# PFC.net
KiCad netlist of a schematic drawn in Altium Designer
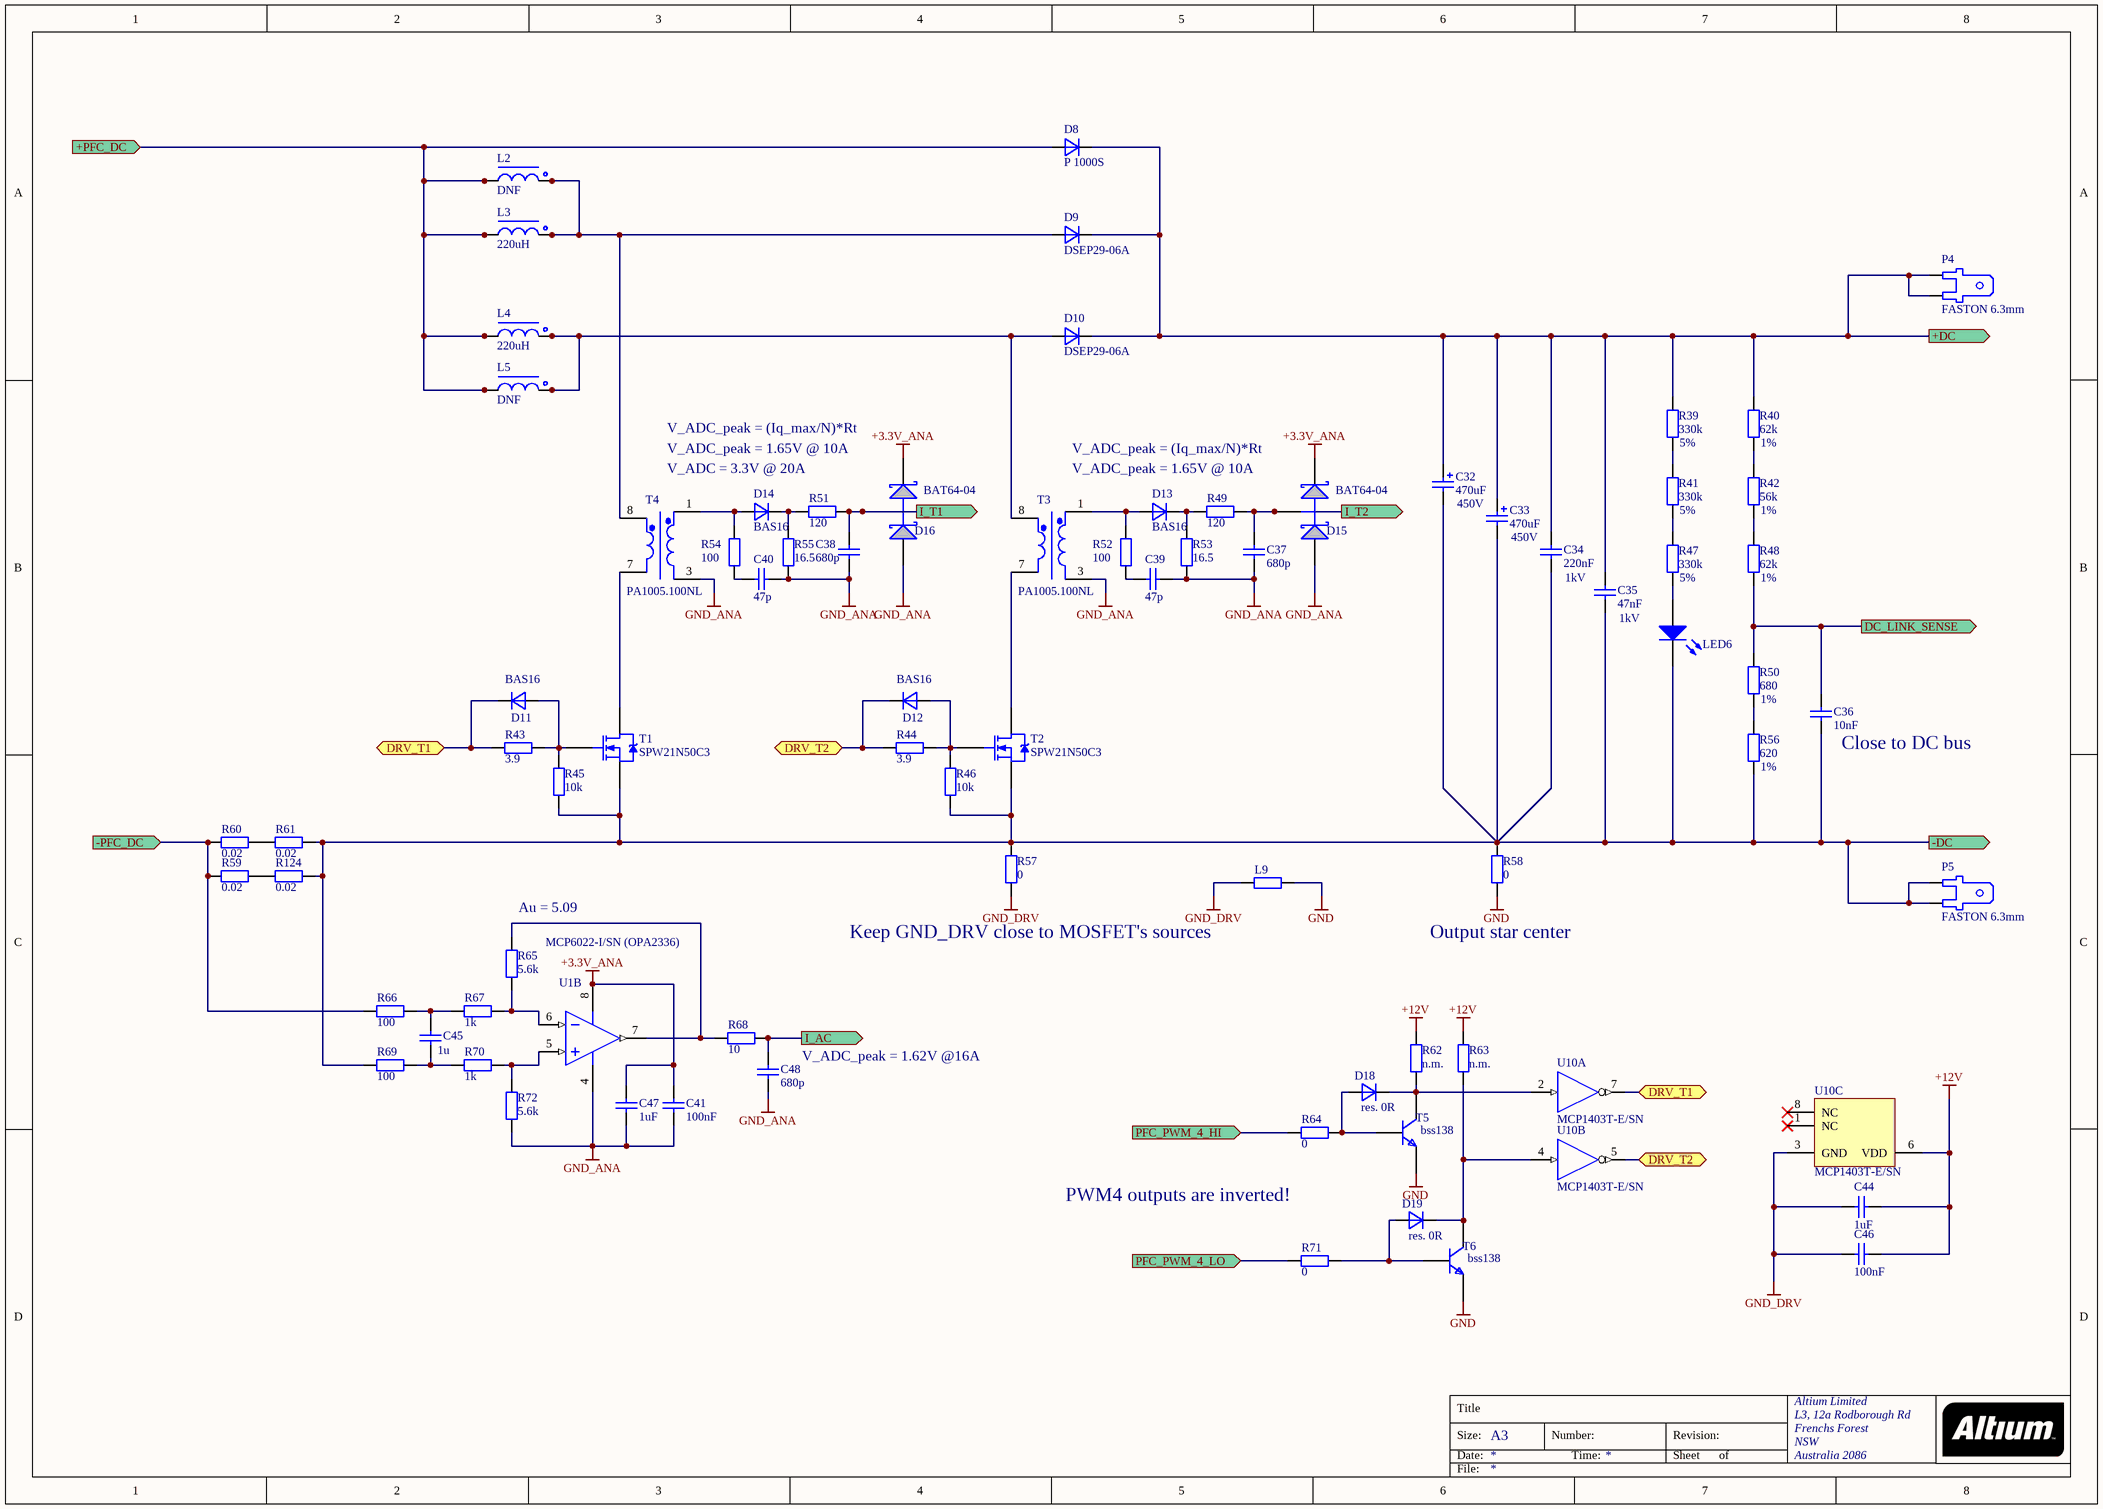
[diagram p0: PFC.SchDoc]

(export (version "E")
  (design (tool "Eeschema 10.0.6"))
  (components
    (comp (ref "C32")
      (value "470uF")
      (footprint "CAPR 52X35")
      (fields (field (name "VOLTAGE") "450V") (field (name "Comment") "Cap"))
      (libsource (lib "Capacitors") (part "Cap pol"))
    )
    (comp (ref "C33")
      (value "470uF")
      (footprint "CAPR 52X35")
      (fields (field (name "VOLTAGE") "450V") (field (name "Comment") "Cap"))
      (libsource (lib "Capacitors") (part "Cap pol"))
    )
    (comp (ref "C34")
      (value "220nF")
      (footprint "RECT 31.0X11.0 RM27.5")
      (fields
        (field (name "VOLTAGE") "1kV")
        (field (name "MANUFACTURER") "EPCOS")
        (field (name "Comment") "Cap")
      )
      (libsource (lib "Capacitors") (part "Cap"))
    )
    (comp (ref "C35")
      (value "47nF")
      (footprint "RECT 26.5X7.0 RM22.5")
      (fields
        (field (name "VOLTAGE") "1kV")
        (field (name "MANUFACTURER") "Epcos")
        (field (name "Comment") "Cap")
      )
      (libsource (lib "Capacitors") (part "Cap"))
    )
    (comp (ref "C36")
      (value "10nF")
      (footprint "1206_REFLOW")
      (fields (field (name "Comment") "Cap 1206"))
      (libsource (lib "Capacitors") (part "Cap 1206"))
    )
    (comp (ref "C37")
      (value "680p")
      (footprint "1206_REFLOW")
      (fields (field (name "Comment") "Cap 1206"))
      (libsource (lib "Capacitors") (part "Cap 1206"))
    )
    (comp (ref "C38")
      (value "680p")
      (footprint "1206_REFLOW")
      (fields (field (name "Comment") "Cap 1206"))
      (libsource (lib "Capacitors") (part "Cap 1206"))
    )
    (comp (ref "C39")
      (value "47p")
      (footprint "1206_REFLOW")
      (fields (field (name "Comment") "Cap 1206"))
      (libsource (lib "Capacitors") (part "Cap 1206"))
    )
    (comp (ref "C40")
      (value "47p")
      (footprint "1206_REFLOW")
      (fields (field (name "Comment") "Cap 1206"))
      (libsource (lib "Capacitors") (part "Cap 1206"))
    )
    (comp (ref "C41")
      (value "100nF")
      (footprint "1206_REFLOW")
      (fields (field (name "Comment") "Cap"))
      (libsource (lib "Capacitors") (part "Cap"))
    )
    (comp (ref "C44")
      (value "1uF")
      (footprint "1206_REFLOW")
      (fields (field (name "Comment") "Cap 1206"))
      (libsource (lib "Capacitors") (part "Cap 1206"))
    )
    (comp (ref "C45")
      (value "1u")
      (footprint "1206_REFLOW")
      (fields (field (name "Comment") "Cap"))
      (libsource (lib "Capacitors") (part "Cap"))
    )
    (comp (ref "C46")
      (value "100nF")
      (footprint "1206_REFLOW")
      (fields (field (name "Comment") "Cap 1206"))
      (libsource (lib "Capacitors") (part "Cap 1206"))
    )
    (comp (ref "C47")
      (value "1uF")
      (footprint "1206_REFLOW")
      (fields (field (name "Comment") "Cap"))
      (libsource (lib "Capacitors") (part "Cap"))
    )
    (comp (ref "C48")
      (value "680p")
      (footprint "1206_REFLOW")
      (fields (field (name "Comment") "Cap"))
      (libsource (lib "Capacitors") (part "Cap"))
    )
    (comp (ref "D8")
      (value "P 1000S")
      (footprint "P 1000 S")
      (description "Standard silicon rectifier  diode")
      (libsource (lib "Diode") (part "P 1000S"))
    )
    (comp (ref "D9")
      (value "DSEP29-06A")
      (footprint "Diode TO-220AC-HV")
      (description "HiPerFREDTM Epitaxial Diode with soft recovery")
      (libsource (lib "Diode") (part "DSEP29-06A"))
    )
    (comp (ref "D10")
      (value "DSEP29-06A")
      (footprint "Diode TO-220AC-HV")
      (description "HiPerFREDTM Epitaxial Diode with soft recovery")
      (libsource (lib "Diode") (part "DSEP29-06A"))
    )
    (comp (ref "D11")
      (value "BAS16")
      (footprint "SOT23_HIS_Primary")
      (description "DIODE, SINGLE SOT-23")
      (fields (field (name "MANUFACTURER") "Any"))
      (libsource (lib "") (part "BAS16_1"))
    )
    (comp (ref "D12")
      (value "BAS16")
      (footprint "SOT23_HIS_Primary")
      (description "DIODE, SINGLE SOT-23")
      (fields (field (name "MANUFACTURER") "Any"))
      (libsource (lib "") (part "BAS16_1"))
    )
    (comp (ref "D13")
      (value "BAS16")
      (footprint "SOT23_HIS_Primary")
      (description "DIODE, SINGLE SOT-23")
      (fields (field (name "MANUFACTURER") "Any"))
      (libsource (lib "Diode") (part "BAS16"))
    )
    (comp (ref "D14")
      (value "BAS16")
      (footprint "SOT23_HIS_Primary")
      (description "DIODE, SINGLE SOT-23")
      (fields (field (name "MANUFACTURER") "Any"))
      (libsource (lib "Diode") (part "BAS16"))
    )
    (comp (ref "D15")
      (value "BAT64-04")
      (footprint "SOT23_HIS_Primary")
      (description "Silicon Schottky Diodes")
      (fields (field (name "MANUFACTURER") "INF") (field (name "PUBLISHER") "Altium Limited"))
      (libsource (lib "Diode") (part "BAT64-04"))
    )
    (comp (ref "D16")
      (value "BAT64-04")
      (footprint "SOT23_HIS_Primary")
      (description "Silicon Schottky Diodes")
      (fields (field (name "MANUFACTURER") "INF") (field (name "PUBLISHER") "Altium Limited"))
      (libsource (lib "Diode") (part "BAT64-04"))
    )
    (comp (ref "D18")
      (value "res. 0R")
      (footprint "SOT23_HIS_Primary")
      (description "DIODE, SINGLE SOT-23")
      (fields (field (name "MANUFACTURER") "Any") (field (name "Comment") "BAS16"))
      (libsource (lib "Diode") (part "BAS16"))
    )
    (comp (ref "D19")
      (value "res. 0R")
      (footprint "SOT23_HIS_Primary")
      (description "DIODE, SINGLE SOT-23")
      (fields (field (name "MANUFACTURER") "Any") (field (name "Comment") "BAS16"))
      (libsource (lib "Diode") (part "BAS16"))
    )
    (comp (ref "L2")
      (value "DNF")
      (footprint "RM-14")
      (fields (field (name "Comment") "RM-14 Choke"))
      (libsource (lib "Inductor") (part "RM-xx Choke"))
    )
    (comp (ref "L3")
      (value "220uH")
      (footprint "RM-10")
      (fields (field (name "Comment") "RM-10 Choke"))
      (libsource (lib "Inductor") (part "RM-xx Choke"))
    )
    (comp (ref "L4")
      (value "220uH")
      (footprint "RM-10")
      (fields (field (name "Comment") "RM-10 Choke"))
      (libsource (lib "Inductor") (part "RM-xx Choke"))
    )
    (comp (ref "L5")
      (value "DNF")
      (footprint "RM-14")
      (fields (field (name "Comment") "RM-14 Choke"))
      (libsource (lib "Inductor") (part "RM-xx Choke"))
    )
    (comp (ref "L9") (value "RES") (footprint "1206_REFLOW") (libsource (lib "") (part "RES 1_1")))
    (comp (ref "LED6") (value "LED") (footprint "LED_1206") (libsource (lib "LED") (part "LED")))
    (comp (ref "P4")
      (value "FASTON 6.3mm")
      (footprint "FASTON 6.3mm")
      (fields (field (name "Comment") "FASTON 6.3MM"))
      (libsource (lib "Connector") (part "FASTON 6.3MM"))
    )
    (comp (ref "P5")
      (value "FASTON 6.3mm")
      (footprint "FASTON 6.3mm")
      (fields (field (name "Comment") "FASTON 6.3MM"))
      (libsource (lib "Connector") (part "FASTON 6.3MM"))
    )
    (comp (ref "R39")
      (value "330k")
      (footprint "RA161004")
      (fields (field (name "TOLERANCE") "5%") (field (name "Comment") "RES"))
      (libsource (lib "Resistor") (part "RES 1"))
    )
    (comp (ref "R40")
      (value "62k")
      (footprint "RA161004")
      (fields (field (name "TOLERANCE") "1%") (field (name "Comment") "RES"))
      (libsource (lib "Resistor") (part "RES 1"))
    )
    (comp (ref "R41")
      (value "330k")
      (footprint "RA161004")
      (fields (field (name "TOLERANCE") "5%") (field (name "Comment") "RES"))
      (libsource (lib "Resistor") (part "RES 1"))
    )
    (comp (ref "R42")
      (value "56k")
      (footprint "RA161004")
      (fields (field (name "TOLERANCE") "1%") (field (name "Comment") "RES"))
      (libsource (lib "Resistor") (part "RES 1"))
    )
    (comp (ref "R43")
      (value "3.9")
      (footprint "1206_REFLOW")
      (fields (field (name "Comment") "RES"))
      (libsource (lib "") (part "RES 1_1"))
    )
    (comp (ref "R44")
      (value "3.9")
      (footprint "1206_REFLOW")
      (fields (field (name "Comment") "RES"))
      (libsource (lib "") (part "RES 1_3"))
    )
    (comp (ref "R45")
      (value "10k")
      (footprint "1206_REFLOW")
      (fields (field (name "Comment") "RES"))
      (libsource (lib "") (part "RES 1_2"))
    )
    (comp (ref "R46")
      (value "10k")
      (footprint "1206_REFLOW")
      (fields (field (name "Comment") "RES"))
      (libsource (lib "Resistor") (part "RES 1"))
    )
    (comp (ref "R47")
      (value "330k")
      (footprint "RA161004")
      (fields (field (name "TOLERANCE") "5%") (field (name "Comment") "RES"))
      (libsource (lib "Resistor") (part "RES 1"))
    )
    (comp (ref "R48")
      (value "62k")
      (footprint "RA161004")
      (fields (field (name "TOLERANCE") "1%") (field (name "Comment") "RES"))
      (libsource (lib "Resistor") (part "RES 1"))
    )
    (comp (ref "R49")
      (value "120")
      (footprint "1206_REFLOW")
      (fields (field (name "TOLERANCE") "1%") (field (name "Comment") "RES"))
      (libsource (lib "") (part "RES 1_3"))
    )
    (comp (ref "R50")
      (value "680")
      (footprint "RA161004")
      (fields (field (name "TOLERANCE") "1%") (field (name "Comment") "RES"))
      (libsource (lib "Resistor") (part "RES 1"))
    )
    (comp (ref "R51")
      (value "120")
      (footprint "1206_REFLOW")
      (fields (field (name "TOLERANCE") "1%") (field (name "Comment") "RES"))
      (libsource (lib "") (part "RES 1_3"))
    )
    (comp (ref "R52")
      (value "100")
      (footprint "1206_REFLOW")
      (fields (field (name "Comment") "RES"))
      (libsource (lib "") (part "RES 1_2"))
    )
    (comp (ref "R53")
      (value "16.5")
      (footprint "1206_REFLOW")
      (fields (field (name "Comment") "RES"))
      (libsource (lib "") (part "RES 1_2"))
    )
    (comp (ref "R54")
      (value "100")
      (footprint "1206_REFLOW")
      (fields (field (name "Comment") "RES"))
      (libsource (lib "") (part "RES 1_2"))
    )
    (comp (ref "R55")
      (value "16.5")
      (footprint "1206_REFLOW")
      (fields (field (name "Comment") "RES"))
      (libsource (lib "") (part "RES 1_2"))
    )
    (comp (ref "R56")
      (value "620")
      (footprint "RA161004")
      (fields (field (name "TOLERANCE") "1%") (field (name "Comment") "RES"))
      (libsource (lib "Resistor") (part "RES 1"))
    )
    (comp (ref "R57")
      (value "0")
      (footprint "1206_REFLOW")
      (fields (field (name "Comment") "RES"))
      (libsource (lib "Resistor") (part "RES 1"))
    )
    (comp (ref "R58")
      (value "0")
      (footprint "1206_REFLOW")
      (fields (field (name "Comment") "RES"))
      (libsource (lib "Resistor") (part "RES 1"))
    )
    (comp (ref "R59")
      (value "0.02")
      (footprint "2512_REFLOW")
      (description "MULTICOMP - MCPWR12FTEA2005 - RESISTOR, 2512, 20M 1%, 1.5W")
      (fields (field (name "TOLERANCE") "1%") (field (name "MANUFACTURER") "WELWYN"))
      (libsource (lib "") (part "RES 1_1"))
    )
    (comp (ref "R60")
      (value "0.02")
      (footprint "2512_REFLOW")
      (description "MULTICOMP - MCPWR12FTEA2005 - RESISTOR, 2512, 20M 1%, 1.5W")
      (fields (field (name "TOLERANCE") "1%") (field (name "MANUFACTURER") "WELWYN"))
      (libsource (lib "") (part "RES 1_1"))
    )
    (comp (ref "R61")
      (value "0.02")
      (footprint "2512_REFLOW")
      (description "MULTICOMP - MCPWR12FTEA2005 - RESISTOR, 2512, 20M 1%, 1.5W")
      (fields (field (name "TOLERANCE") "1%") (field (name "MANUFACTURER") "WELWYN"))
      (libsource (lib "") (part "RES 1_1"))
    )
    (comp (ref "R62")
      (value "n.m.")
      (footprint "1206_REFLOW")
      (fields (field (name "Comment") "RES"))
      (libsource (lib "Resistor") (part "RES 1"))
    )
    (comp (ref "R63")
      (value "n.m.")
      (footprint "1206_REFLOW")
      (fields (field (name "Comment") "RES"))
      (libsource (lib "Resistor") (part "RES 1"))
    )
    (comp (ref "R64")
      (value "0")
      (footprint "1206_REFLOW")
      (fields (field (name "Comment") "RES"))
      (libsource (lib "") (part "RES 1_1"))
    )
    (comp (ref "R65")
      (value "5.6k")
      (footprint "1206_REFLOW")
      (fields (field (name "TOLERANCE") "1%") (field (name "Comment") "RES"))
      (libsource (lib "") (part "RES 1_2"))
    )
    (comp (ref "R66")
      (value "100")
      (footprint "1206_REFLOW")
      (fields (field (name "TOLERANCE") "1%") (field (name "Comment") "RES"))
      (libsource (lib "") (part "RES 1_1"))
    )
    (comp (ref "R67")
      (value "1k")
      (footprint "1206_REFLOW")
      (fields (field (name "TOLERANCE") "1%") (field (name "Comment") "RES"))
      (libsource (lib "") (part "RES 1_1"))
    )
    (comp (ref "R68")
      (value "10")
      (footprint "1206_REFLOW")
      (fields (field (name "TOLERANCE") "1%") (field (name "Comment") "RES"))
      (libsource (lib "") (part "RES 1_3"))
    )
    (comp (ref "R69")
      (value "100")
      (footprint "1206_REFLOW")
      (fields (field (name "TOLERANCE") "1%") (field (name "Comment") "RES"))
      (libsource (lib "") (part "RES 1_1"))
    )
    (comp (ref "R70")
      (value "1k")
      (footprint "1206_REFLOW")
      (fields (field (name "TOLERANCE") "1%") (field (name "Comment") "RES"))
      (libsource (lib "") (part "RES 1_1"))
    )
    (comp (ref "R71")
      (value "0")
      (footprint "1206_REFLOW")
      (fields (field (name "Comment") "RES"))
      (libsource (lib "") (part "RES 1_1"))
    )
    (comp (ref "R72")
      (value "5.6k")
      (footprint "1206_REFLOW")
      (fields (field (name "TOLERANCE") "1%") (field (name "Comment") "RES"))
      (libsource (lib "") (part "RES 1_2"))
    )
    (comp (ref "R124")
      (value "0.02")
      (footprint "2512_REFLOW")
      (description "MULTICOMP - MCPWR12FTEA2005 - RESISTOR, 2512, 20M 1%, 1.5W")
      (fields (field (name "TOLERANCE") "1%") (field (name "MANUFACTURER") "WELWYN"))
      (libsource (lib "") (part "RES 1_1"))
    )
    (comp (ref "T1")
      (value "SPW21N50C3")
      (footprint "TO-247HV")
      (description "INFINEON - SPW21N50C3 - MOSFET, N, 500V, TO-247")
      (fields (field (name "Comment") "MOSFET, N, 500V, TO-247"))
      (libsource (lib "Transistors") (part "SPW21N50C3"))
    )
    (comp (ref "T2")
      (value "SPW21N50C3")
      (footprint "TO-247HV")
      (description "INFINEON - SPW21N50C3 - MOSFET, N, 500V, TO-247")
      (fields (field (name "Comment") "MOSFET, N, 500V, TO-247"))
      (libsource (lib "Transistors") (part "SPW21N50C3"))
    )
    (comp (ref "T3")
      (value "PA1005.100NL")
      (footprint "PA1005.XXXNL Series")
      (fields
        (field (name "MANUFACTURER") "PULSE ELECTRONICS CORPORATION")
        (field (name "Comment") "PA1005.XXXNL")
      )
      (libsource (lib "Transformer") (part "PA1005.XXXNL Series"))
    )
    (comp (ref "T4")
      (value "PA1005.100NL")
      (footprint "PA1005.XXXNL Series")
      (fields
        (field (name "MANUFACTURER") "PULSE ELECTRONICS CORPORATION")
        (field (name "Comment") "PA1005.XXXNL")
      )
      (libsource (lib "Transformer") (part "PA1005.XXXNL Series"))
    )
    (comp (ref "T5")
      (value "bss138")
      (footprint "SOT23_HIS_Primary")
      (description "NPN General Purpose Amplifier")
      (fields (field (name "Comment") "BC847A"))
      (libsource (lib "Transistor_Bipolar") (part "BC847A"))
    )
    (comp (ref "T6")
      (value "bss138")
      (footprint "SOT23_HIS_Primary")
      (description "NPN General Purpose Amplifier")
      (fields (field (name "Comment") "BC847A"))
      (libsource (lib "Transistor_Bipolar") (part "BC847A"))
    )
    (comp (ref "U1")
      (value "MCP6022-I/SN (OPA2336)")
      (footprint "SOIC-SN8_N")
      (description "Rail-to-Rail Input/Output, 10 MHz Operational Amplifier, 8-Pin SOIC, Industrial Temperature")
      (fields (field (name "PUBLISHER") "Altium Limited"))
      (libsource (lib "Microchip Linear Devices") (part "MCP6022-I/SN"))
    )
    (comp (ref "U10")
      (value "MCP1403T-E/SN")
      (footprint "SOIC-SN8_N")
      (description "4.5A Dual High-Speed Power MOSFET Drivers, Inverting, Extended Temperature, Tape and Reel")
      (fields (field (name "PUBLISHER") "Altium Limited"))
      (libsource (lib "") (part "MCP1403T-E/SN_1"))
    )
  )
  (nets
    (net (code "1") (name "+3.3V_ANA") (class "Default")
      (node (ref "C41") (pin "2") (pinfunction "2_2") (pintype "passive"))
      (node (ref "C47") (pin "2") (pinfunction "2_2") (pintype "passive"))
      (node (ref "D15") (pin "2") (pinfunction "K_2") (pintype "passive"))
      (node (ref "D16") (pin "2") (pinfunction "K_2") (pintype "passive"))
      (node (ref "U1") (pin "8") (pinfunction "VDD_8") (pintype "power_in"))
    )
    (net (code "2") (name "+12V") (class "Default")
      (node (ref "C44") (pin "1") (pinfunction "1_1") (pintype "passive"))
      (node (ref "C46") (pin "1") (pinfunction "1_1") (pintype "passive"))
      (node (ref "R62") (pin "1") (pinfunction "1_1") (pintype "passive"))
      (node (ref "R63") (pin "1") (pinfunction "1_1") (pintype "passive"))
      (node (ref "U10") (pin "6") (pinfunction "VDD_6") (pintype "power_in"))
    )
    (net (code "3") (name "/+DC") (class "Default")
      (node (ref "C32") (pin "1") (pinfunction "1_1") (pintype "passive"))
      (node (ref "C33") (pin "1") (pinfunction "1_1") (pintype "passive"))
      (node (ref "C34") (pin "2") (pinfunction "2_2") (pintype "passive"))
      (node (ref "C35") (pin "2") (pinfunction "2_2") (pintype "passive"))
      (node (ref "D10") (pin "1") (pinfunction "K_1") (pintype "passive"))
      (node (ref "D8") (pin "K") (pintype "passive"))
      (node (ref "D9") (pin "1") (pinfunction "K_1") (pintype "passive"))
      (node (ref "P4") (pin "1") (pinfunction "1_1") (pintype "passive"))
      (node (ref "P4") (pin "2") (pinfunction "2_2") (pintype "passive"))
      (node (ref "R39") (pin "1") (pinfunction "1_1") (pintype "passive"))
      (node (ref "R40") (pin "1") (pinfunction "1_1") (pintype "passive"))
    )
    (net (code "4") (name "/+PFC_DC") (class "Default")
      (node (ref "D8") (pin "A") (pintype "passive"))
      (node (ref "L2") (pin "10") (pinfunction "10_10") (pintype "passive"))
      (node (ref "L2") (pin "11") (pinfunction "11_11") (pintype "passive"))
      (node (ref "L2") (pin "12") (pinfunction "12_12") (pintype "passive"))
      (node (ref "L2") (pin "7") (pinfunction "7_7") (pintype "passive"))
      (node (ref "L2") (pin "8") (pinfunction "8_8") (pintype "passive"))
      (node (ref "L2") (pin "9") (pinfunction "9_9") (pintype "passive"))
      (node (ref "L3") (pin "10") (pinfunction "10_10") (pintype "passive"))
      (node (ref "L3") (pin "11") (pinfunction "11_11") (pintype "passive"))
      (node (ref "L3") (pin "12") (pinfunction "12_12") (pintype "passive"))
      (node (ref "L3") (pin "7") (pinfunction "7_7") (pintype "passive"))
      (node (ref "L3") (pin "8") (pinfunction "8_8") (pintype "passive"))
      (node (ref "L3") (pin "9") (pinfunction "9_9") (pintype "passive"))
      (node (ref "L4") (pin "10") (pinfunction "10_10") (pintype "passive"))
      (node (ref "L4") (pin "11") (pinfunction "11_11") (pintype "passive"))
      (node (ref "L4") (pin "12") (pinfunction "12_12") (pintype "passive"))
      (node (ref "L4") (pin "7") (pinfunction "7_7") (pintype "passive"))
      (node (ref "L4") (pin "8") (pinfunction "8_8") (pintype "passive"))
      (node (ref "L4") (pin "9") (pinfunction "9_9") (pintype "passive"))
      (node (ref "L5") (pin "10") (pinfunction "10_10") (pintype "passive"))
      (node (ref "L5") (pin "11") (pinfunction "11_11") (pintype "passive"))
      (node (ref "L5") (pin "12") (pinfunction "12_12") (pintype "passive"))
      (node (ref "L5") (pin "7") (pinfunction "7_7") (pintype "passive"))
      (node (ref "L5") (pin "8") (pinfunction "8_8") (pintype "passive"))
      (node (ref "L5") (pin "9") (pinfunction "9_9") (pintype "passive"))
    )
    (net (code "5") (name "/-DC") (class "Default")
      (node (ref "C32") (pin "2") (pinfunction "2_2") (pintype "passive"))
      (node (ref "C33") (pin "2") (pinfunction "2_2") (pintype "passive"))
      (node (ref "C34") (pin "1") (pinfunction "1_1") (pintype "passive"))
      (node (ref "C35") (pin "1") (pinfunction "1_1") (pintype "passive"))
      (node (ref "C36") (pin "1") (pinfunction "1_1") (pintype "passive"))
      (node (ref "LED6") (pin "K") (pinfunction "K_K") (pintype "passive"))
      (node (ref "P5") (pin "1") (pinfunction "1_1") (pintype "passive"))
      (node (ref "P5") (pin "2") (pinfunction "2_2") (pintype "passive"))
      (node (ref "R124") (pin "2") (pinfunction "2_2") (pintype "passive"))
      (node (ref "R45") (pin "1") (pinfunction "1_1") (pintype "passive"))
      (node (ref "R46") (pin "2") (pinfunction "2_2") (pintype "passive"))
      (node (ref "R56") (pin "2") (pinfunction "2_2") (pintype "passive"))
      (node (ref "R57") (pin "1") (pinfunction "1_1") (pintype "passive"))
      (node (ref "R58") (pin "1") (pinfunction "1_1") (pintype "passive"))
      (node (ref "R61") (pin "2") (pinfunction "2_2") (pintype "passive"))
      (node (ref "R69") (pin "1") (pinfunction "1_1") (pintype "passive"))
      (node (ref "T1") (pin "3") (pinfunction "S_3") (pintype "passive"))
      (node (ref "T2") (pin "3") (pinfunction "S_3") (pintype "passive"))
    )
    (net (code "6") (name "/-PFC_DC") (class "Default")
      (node (ref "R59") (pin "1") (pinfunction "1_1") (pintype "passive"))
      (node (ref "R60") (pin "1") (pinfunction "1_1") (pintype "passive"))
      (node (ref "R66") (pin "1") (pinfunction "1_1") (pintype "passive"))
    )
    (net (code "7") (name "/DC_LINK_SENSE") (class "Default")
      (node (ref "C36") (pin "2") (pinfunction "2_2") (pintype "passive"))
      (node (ref "R48") (pin "2") (pinfunction "2_2") (pintype "passive"))
      (node (ref "R50") (pin "1") (pinfunction "1_1") (pintype "passive"))
    )
    (net (code "8") (name "/DRV_T1") (class "Default")
      (node (ref "D11") (pin "3") (pinfunction "K_3") (pintype "passive"))
      (node (ref "R43") (pin "1") (pinfunction "1_1") (pintype "passive"))
      (node (ref "U10") (pin "7") (pinfunction "~{OUTA}_7") (pintype "output"))
    )
    (net (code "9") (name "/DRV_T2") (class "Default")
      (node (ref "D12") (pin "3") (pinfunction "K_3") (pintype "passive"))
      (node (ref "R44") (pin "2") (pinfunction "2_2") (pintype "passive"))
      (node (ref "U10") (pin "5") (pinfunction "~{OUTB}_5") (pintype "output"))
    )
    (net (code "10") (name "/I_AC") (class "Default")
      (node (ref "C48") (pin "2") (pinfunction "2_2") (pintype "passive"))
      (node (ref "R68") (pin "1") (pinfunction "1_1") (pintype "passive"))
    )
    (net (code "11") (name "/I_T1") (class "Default")
      (node (ref "C38") (pin "1") (pinfunction "1_1") (pintype "passive"))
      (node (ref "D16") (pin "3") (pinfunction "C_3") (pintype "passive"))
      (node (ref "R51") (pin "1") (pinfunction "1_1") (pintype "passive"))
    )
    (net (code "12") (name "/I_T2") (class "Default")
      (node (ref "C37") (pin "1") (pinfunction "1_1") (pintype "passive"))
      (node (ref "D15") (pin "3") (pinfunction "C_3") (pintype "passive"))
      (node (ref "R49") (pin "1") (pinfunction "1_1") (pintype "passive"))
    )
    (net (code "13") (name "/PFC_PWM_4_HI") (class "Default")
      (node (ref "R64") (pin "1") (pinfunction "1_1") (pintype "passive"))
    )
    (net (code "14") (name "/PFC_PWM_4_LO") (class "Default")
      (node (ref "R71") (pin "1") (pinfunction "1_1") (pintype "passive"))
    )
    (net (code "15") (name "GND") (class "Default")
      (node (ref "L9") (pin "2") (pinfunction "2_2") (pintype "passive"))
      (node (ref "R58") (pin "2") (pinfunction "2_2") (pintype "passive"))
      (node (ref "T5") (pin "2") (pinfunction "E_2") (pintype "passive"))
      (node (ref "T6") (pin "2") (pinfunction "E_2") (pintype "passive"))
    )
    (net (code "16") (name "GND_ANA") (class "Default")
      (node (ref "C37") (pin "2") (pinfunction "2_2") (pintype "passive"))
      (node (ref "C38") (pin "2") (pinfunction "2_2") (pintype "passive"))
      (node (ref "C39") (pin "1") (pinfunction "1_1") (pintype "passive"))
      (node (ref "C40") (pin "1") (pinfunction "1_1") (pintype "passive"))
      (node (ref "C41") (pin "1") (pinfunction "1_1") (pintype "passive"))
      (node (ref "C47") (pin "1") (pinfunction "1_1") (pintype "passive"))
      (node (ref "C48") (pin "1") (pinfunction "1_1") (pintype "passive"))
      (node (ref "D15") (pin "1") (pinfunction "A_1") (pintype "passive"))
      (node (ref "D16") (pin "1") (pinfunction "A_1") (pintype "passive"))
      (node (ref "R53") (pin "1") (pinfunction "1_1") (pintype "passive"))
      (node (ref "R55") (pin "1") (pinfunction "1_1") (pintype "passive"))
      (node (ref "R72") (pin "1") (pinfunction "1_1") (pintype "passive"))
      (node (ref "T3") (pin "3") (pinfunction "Sec2+_3") (pintype "passive"))
      (node (ref "T4") (pin "3") (pinfunction "Sec2+_3") (pintype "passive"))
      (node (ref "U1") (pin "4") (pinfunction "VSS_4") (pintype "power_in"))
    )
    (net (code "17") (name "GND_DRV") (class "Default")
      (node (ref "C44") (pin "2") (pinfunction "2_2") (pintype "passive"))
      (node (ref "C46") (pin "2") (pinfunction "2_2") (pintype "passive"))
      (node (ref "L9") (pin "1") (pinfunction "1_1") (pintype "passive"))
      (node (ref "R57") (pin "2") (pinfunction "2_2") (pintype "passive"))
      (node (ref "U10") (pin "3") (pinfunction "GND_3") (pintype "power_in"))
    )
    (net (code "18") (name "Net-(C39-Pad2)") (class "Default")
      (node (ref "C39") (pin "2") (pinfunction "2_2") (pintype "passive"))
      (node (ref "R52") (pin "1") (pinfunction "1_1") (pintype "passive"))
    )
    (net (code "19") (name "Net-(C40-Pad2)") (class "Default")
      (node (ref "C40") (pin "2") (pinfunction "2_2") (pintype "passive"))
      (node (ref "R54") (pin "1") (pinfunction "1_1") (pintype "passive"))
    )
    (net (code "20") (name "Net-(C45-Pad1)") (class "Default")
      (node (ref "C45") (pin "1") (pinfunction "1_1") (pintype "passive"))
      (node (ref "R69") (pin "2") (pinfunction "2_2") (pintype "passive"))
      (node (ref "R70") (pin "1") (pinfunction "1_1") (pintype "passive"))
    )
    (net (code "21") (name "Net-(C45-Pad2)") (class "Default")
      (node (ref "C45") (pin "2") (pinfunction "2_2") (pintype "passive"))
      (node (ref "R66") (pin "2") (pinfunction "2_2") (pintype "passive"))
      (node (ref "R67") (pin "1") (pinfunction "1_1") (pintype "passive"))
    )
    (net (code "22") (name "Net-(D9-A)") (class "Default")
      (node (ref "D9") (pin "2") (pinfunction "A_2") (pintype "passive"))
      (node (ref "L2") (pin "1") (pinfunction "1_1") (pintype "passive"))
      (node (ref "L2") (pin "2") (pinfunction "2_2") (pintype "passive"))
      (node (ref "L2") (pin "3") (pinfunction "3_3") (pintype "passive"))
      (node (ref "L2") (pin "4") (pinfunction "4_4") (pintype "passive"))
      (node (ref "L2") (pin "5") (pinfunction "5_5") (pintype "passive"))
      (node (ref "L2") (pin "6") (pinfunction "6_6") (pintype "passive"))
      (node (ref "L3") (pin "1") (pinfunction "1_1") (pintype "passive"))
      (node (ref "L3") (pin "2") (pinfunction "2_2") (pintype "passive"))
      (node (ref "L3") (pin "3") (pinfunction "3_3") (pintype "passive"))
      (node (ref "L3") (pin "4") (pinfunction "4_4") (pintype "passive"))
      (node (ref "L3") (pin "5") (pinfunction "5_5") (pintype "passive"))
      (node (ref "L3") (pin "6") (pinfunction "6_6") (pintype "passive"))
      (node (ref "T4") (pin "8") (pinfunction "Pri+_8") (pintype "passive"))
    )
    (net (code "23") (name "Net-(D10-A)") (class "Default")
      (node (ref "D10") (pin "2") (pinfunction "A_2") (pintype "passive"))
      (node (ref "L4") (pin "1") (pinfunction "1_1") (pintype "passive"))
      (node (ref "L4") (pin "2") (pinfunction "2_2") (pintype "passive"))
      (node (ref "L4") (pin "3") (pinfunction "3_3") (pintype "passive"))
      (node (ref "L4") (pin "4") (pinfunction "4_4") (pintype "passive"))
      (node (ref "L4") (pin "5") (pinfunction "5_5") (pintype "passive"))
      (node (ref "L4") (pin "6") (pinfunction "6_6") (pintype "passive"))
      (node (ref "L5") (pin "1") (pinfunction "1_1") (pintype "passive"))
      (node (ref "L5") (pin "2") (pinfunction "2_2") (pintype "passive"))
      (node (ref "L5") (pin "3") (pinfunction "3_3") (pintype "passive"))
      (node (ref "L5") (pin "4") (pinfunction "4_4") (pintype "passive"))
      (node (ref "L5") (pin "5") (pinfunction "5_5") (pintype "passive"))
      (node (ref "L5") (pin "6") (pinfunction "6_6") (pintype "passive"))
      (node (ref "T3") (pin "8") (pinfunction "Pri+_8") (pintype "passive"))
    )
    (net (code "24") (name "Net-(D11-A)") (class "Default")
      (node (ref "D11") (pin "1") (pinfunction "A_1") (pintype "passive"))
      (node (ref "R43") (pin "2") (pinfunction "2_2") (pintype "passive"))
      (node (ref "R45") (pin "2") (pinfunction "2_2") (pintype "passive"))
      (node (ref "T1") (pin "1") (pinfunction "G_1") (pintype "passive"))
    )
    (net (code "25") (name "Net-(D12-A)") (class "Default")
      (node (ref "D12") (pin "1") (pinfunction "A_1") (pintype "passive"))
      (node (ref "R44") (pin "1") (pinfunction "1_1") (pintype "passive"))
      (node (ref "R46") (pin "1") (pinfunction "1_1") (pintype "passive"))
      (node (ref "T2") (pin "1") (pinfunction "G_1") (pintype "passive"))
    )
    (net (code "26") (name "Net-(D13-A)") (class "Default")
      (node (ref "D13") (pin "1") (pinfunction "A_1") (pintype "passive"))
      (node (ref "R52") (pin "2") (pinfunction "2_2") (pintype "passive"))
      (node (ref "T3") (pin "1") (pinfunction "Sec1+_1") (pintype "passive"))
    )
    (net (code "27") (name "Net-(D13-K)") (class "Default")
      (node (ref "D13") (pin "3") (pinfunction "K_3") (pintype "passive"))
      (node (ref "R49") (pin "2") (pinfunction "2_2") (pintype "passive"))
      (node (ref "R53") (pin "2") (pinfunction "2_2") (pintype "passive"))
    )
    (net (code "28") (name "Net-(D14-A)") (class "Default")
      (node (ref "D14") (pin "1") (pinfunction "A_1") (pintype "passive"))
      (node (ref "R54") (pin "2") (pinfunction "2_2") (pintype "passive"))
      (node (ref "T4") (pin "1") (pinfunction "Sec1+_1") (pintype "passive"))
    )
    (net (code "29") (name "Net-(D14-K)") (class "Default")
      (node (ref "D14") (pin "3") (pinfunction "K_3") (pintype "passive"))
      (node (ref "R51") (pin "2") (pinfunction "2_2") (pintype "passive"))
      (node (ref "R55") (pin "2") (pinfunction "2_2") (pintype "passive"))
    )
    (net (code "30") (name "Net-(D18-A)") (class "Default")
      (node (ref "D18") (pin "1") (pinfunction "A_1") (pintype "passive"))
      (node (ref "R64") (pin "2") (pinfunction "2_2") (pintype "passive"))
      (node (ref "T5") (pin "1") (pinfunction "B_1") (pintype "passive"))
    )
    (net (code "31") (name "Net-(D18-K)") (class "Default")
      (node (ref "D18") (pin "3") (pinfunction "K_3") (pintype "passive"))
      (node (ref "R62") (pin "2") (pinfunction "2_2") (pintype "passive"))
      (node (ref "T5") (pin "3") (pinfunction "C_3") (pintype "passive"))
      (node (ref "U10") (pin "2") (pinfunction "INA_2") (pintype "input"))
    )
    (net (code "32") (name "Net-(D19-A)") (class "Default")
      (node (ref "D19") (pin "1") (pinfunction "A_1") (pintype "passive"))
      (node (ref "R71") (pin "2") (pinfunction "2_2") (pintype "passive"))
      (node (ref "T6") (pin "1") (pinfunction "B_1") (pintype "passive"))
    )
    (net (code "33") (name "Net-(D19-K)") (class "Default")
      (node (ref "D19") (pin "3") (pinfunction "K_3") (pintype "passive"))
      (node (ref "R63") (pin "2") (pinfunction "2_2") (pintype "passive"))
      (node (ref "T6") (pin "3") (pinfunction "C_3") (pintype "passive"))
      (node (ref "U10") (pin "4") (pinfunction "INB_4") (pintype "input"))
    )
    (net (code "34") (name "Net-(LED6-PadA)") (class "Default")
      (node (ref "LED6") (pin "A") (pinfunction "A_A") (pintype "passive"))
      (node (ref "R47") (pin "2") (pinfunction "2_2") (pintype "passive"))
    )
    (net (code "35") (name "Net-(R39-Pad2)") (class "Default")
      (node (ref "R39") (pin "2") (pinfunction "2_2") (pintype "passive"))
      (node (ref "R41") (pin "1") (pinfunction "1_1") (pintype "passive"))
    )
    (net (code "36") (name "Net-(R40-Pad2)") (class "Default")
      (node (ref "R40") (pin "2") (pinfunction "2_2") (pintype "passive"))
      (node (ref "R42") (pin "1") (pinfunction "1_1") (pintype "passive"))
    )
    (net (code "37") (name "Net-(R41-Pad2)") (class "Default")
      (node (ref "R41") (pin "2") (pinfunction "2_2") (pintype "passive"))
      (node (ref "R47") (pin "1") (pinfunction "1_1") (pintype "passive"))
    )
    (net (code "38") (name "Net-(R42-Pad2)") (class "Default")
      (node (ref "R42") (pin "2") (pinfunction "2_2") (pintype "passive"))
      (node (ref "R48") (pin "1") (pinfunction "1_1") (pintype "passive"))
    )
    (net (code "39") (name "Net-(R50-Pad2)") (class "Default")
      (node (ref "R50") (pin "2") (pinfunction "2_2") (pintype "passive"))
      (node (ref "R56") (pin "1") (pinfunction "1_1") (pintype "passive"))
    )
    (net (code "40") (name "Net-(R60-Pad2)") (class "Default")
      (node (ref "R60") (pin "2") (pinfunction "2_2") (pintype "passive"))
      (node (ref "R61") (pin "1") (pinfunction "1_1") (pintype "passive"))
    )
    (net (code "41") (name "Net-(R124-Pad1)") (class "Default")
      (node (ref "R124") (pin "1") (pinfunction "1_1") (pintype "passive"))
      (node (ref "R59") (pin "2") (pinfunction "2_2") (pintype "passive"))
    )
    (net (code "42") (name "Net-(T1-D)") (class "Default")
      (node (ref "T1") (pin "2") (pinfunction "D_2") (pintype "passive"))
      (node (ref "T4") (pin "7") (pinfunction "Pri-_7") (pintype "passive"))
    )
    (net (code "43") (name "Net-(T2-D)") (class "Default")
      (node (ref "T2") (pin "2") (pinfunction "D_2") (pintype "passive"))
      (node (ref "T3") (pin "7") (pinfunction "Pri-_7") (pintype "passive"))
    )
    (net (code "44") (name "Net-(U1B-VINB+)") (class "Default")
      (node (ref "R70") (pin "2") (pinfunction "2_2") (pintype "passive"))
      (node (ref "R72") (pin "2") (pinfunction "2_2") (pintype "passive"))
      (node (ref "U1") (pin "5") (pinfunction "VINB+_5") (pintype "input"))
    )
    (net (code "45") (name "Net-(U1B-VINB-)") (class "Default")
      (node (ref "R65") (pin "1") (pinfunction "1_1") (pintype "passive"))
      (node (ref "R67") (pin "2") (pinfunction "2_2") (pintype "passive"))
      (node (ref "U1") (pin "6") (pinfunction "VINB-_6") (pintype "input"))
    )
    (net (code "46") (name "Net-(U1B-VOUTB)") (class "Default")
      (node (ref "R65") (pin "2") (pinfunction "2_2") (pintype "passive"))
      (node (ref "R68") (pin "2") (pinfunction "2_2") (pintype "passive"))
      (node (ref "U1") (pin "7") (pinfunction "VOUTB_7") (pintype "output"))
    )
    (net (code "47") (name "unconnected-(D11-NC-Pad2)") (class "Default")
      (node (ref "D11") (pin "2") (pinfunction "NC_2") (pintype "passive"))
    )
    (net (code "48") (name "unconnected-(D12-NC-Pad2)") (class "Default")
      (node (ref "D12") (pin "2") (pinfunction "NC_2") (pintype "passive"))
    )
    (net (code "49") (name "unconnected-(D13-NC-Pad2)") (class "Default")
      (node (ref "D13") (pin "2") (pinfunction "NC_2") (pintype "passive"))
    )
    (net (code "50") (name "unconnected-(D14-NC-Pad2)") (class "Default")
      (node (ref "D14") (pin "2") (pinfunction "NC_2") (pintype "passive"))
    )
    (net (code "51") (name "unconnected-(D18-NC-Pad2)") (class "Default")
      (node (ref "D18") (pin "2") (pinfunction "NC_2") (pintype "passive"))
    )
    (net (code "52") (name "unconnected-(D19-NC-Pad2)") (class "Default")
      (node (ref "D19") (pin "2") (pinfunction "NC_2") (pintype "passive"))
    )
    (net (code "53") (name "unconnected-(U10C-NC-Pad1)") (class "Default")
      (node (ref "U10") (pin "1") (pinfunction "NC_1") (pintype "passive+no_connect"))
    )
    (net (code "54") (name "unconnected-(U10C-NC-Pad8)") (class "Default")
      (node (ref "U10") (pin "8") (pinfunction "NC_8") (pintype "passive+no_connect"))
    )
  )
)
